# Dual_Driver.net
KiCad netlist of a schematic drawn in EasyEDA Pro
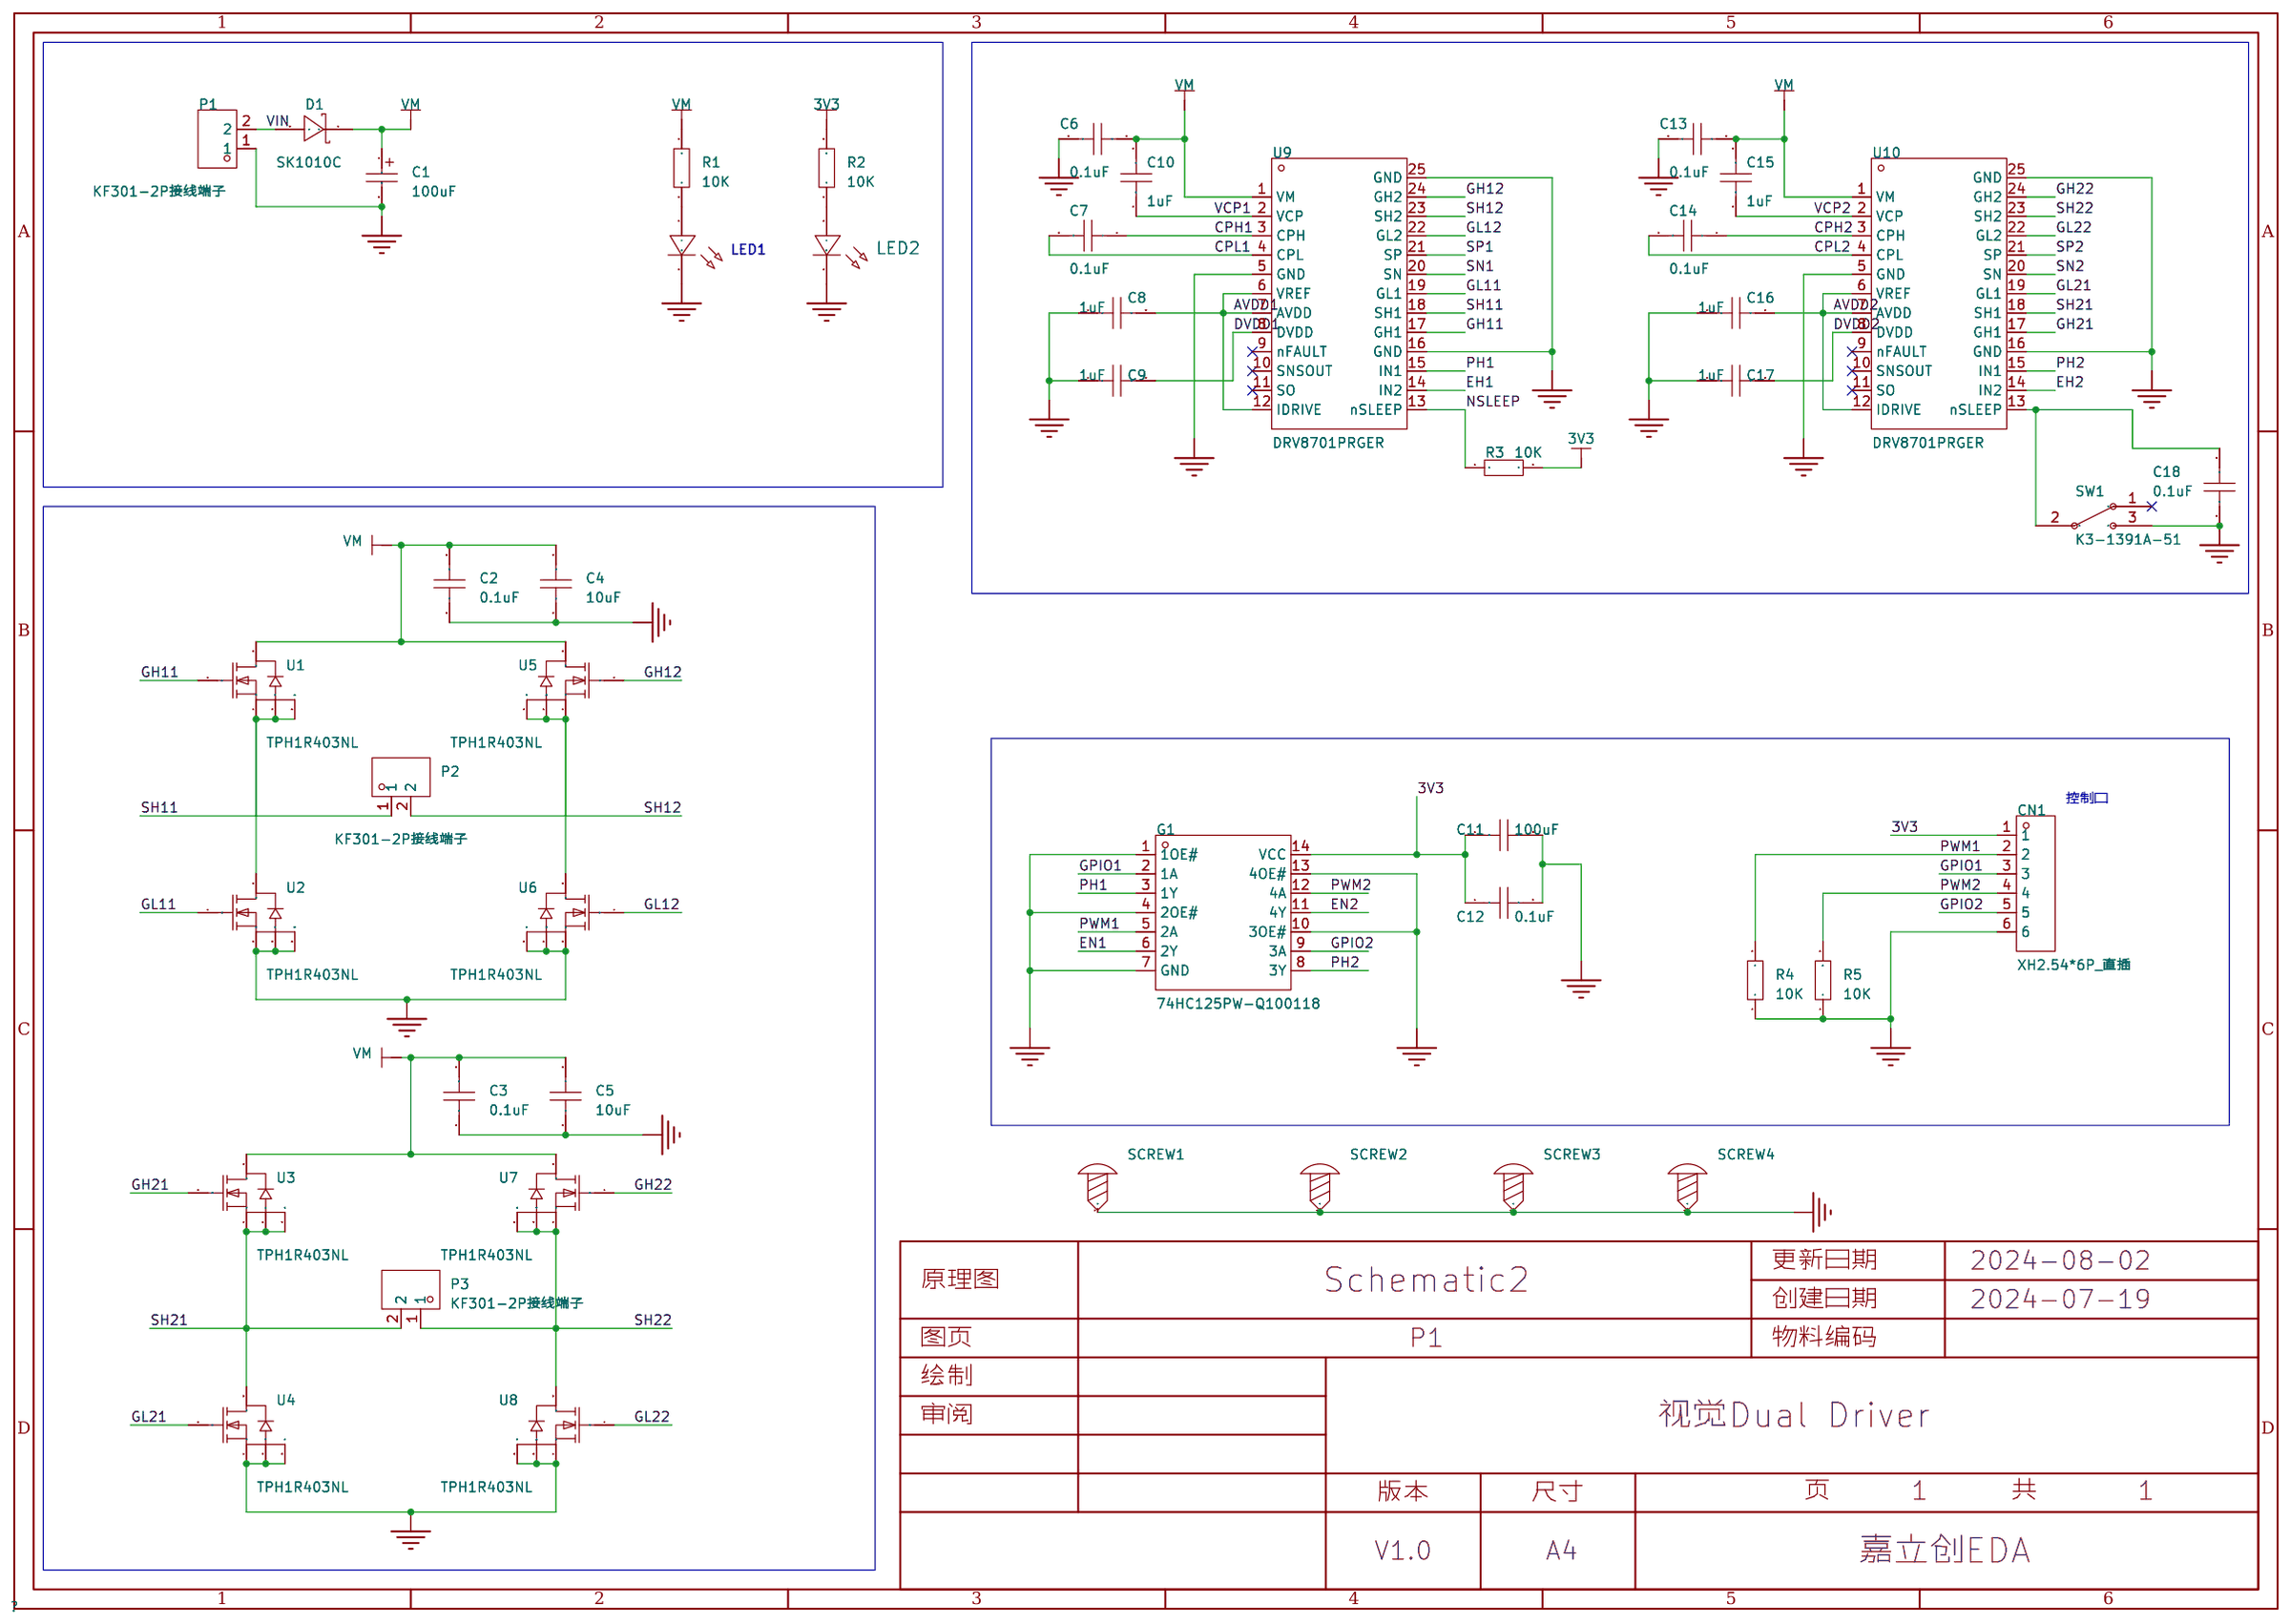
[diagram p0: schematic sheet]

(export (version "E")
  (design (tool "Eeschema 10.0.6"))
  (components
    (comp (ref "C1")
      (value "100uF")
      (footprint "easyedapro:C_Ele_SMD_3x5.4mm")
      (libsource (lib "easyedapro") (part "CAP"))
    )
    (comp (ref "C2")
      (value "0.1uF")
      (footprint "easyedapro:C0603")
      (libsource (lib "easyedapro") (part "CapAcitance"))
    )
    (comp (ref "C3")
      (value "0.1uF")
      (footprint "easyedapro:C0603")
      (libsource (lib "easyedapro") (part "CapAcitance"))
    )
    (comp (ref "C4")
      (value "10uF")
      (footprint "easyedapro:C0603")
      (libsource (lib "easyedapro") (part "CapAcitance"))
    )
    (comp (ref "C5")
      (value "10uF")
      (footprint "easyedapro:C0603")
      (libsource (lib "easyedapro") (part "CapAcitance"))
    )
    (comp (ref "C6")
      (value "0.1uF")
      (footprint "easyedapro:C0603")
      (libsource (lib "easyedapro") (part "CapAcitance"))
    )
    (comp (ref "C7")
      (value "0.1uF")
      (footprint "easyedapro:C0603")
      (libsource (lib "easyedapro") (part "CapAcitance"))
    )
    (comp (ref "C8")
      (value "1uF")
      (footprint "easyedapro:C0603")
      (libsource (lib "easyedapro") (part "CapAcitance"))
    )
    (comp (ref "C9")
      (value "1uF")
      (footprint "easyedapro:C0603")
      (libsource (lib "easyedapro") (part "CapAcitance"))
    )
    (comp (ref "C10")
      (value "1uF")
      (footprint "easyedapro:C0603")
      (libsource (lib "easyedapro") (part "CapAcitance"))
    )
    (comp (ref "C11")
      (value "100uF")
      (footprint "easyedapro:C0603")
      (libsource (lib "easyedapro") (part "CapAcitance"))
    )
    (comp (ref "C12")
      (value "0.1uF")
      (footprint "easyedapro:C0603")
      (libsource (lib "easyedapro") (part "CapAcitance"))
    )
    (comp (ref "C13")
      (value "0.1uF")
      (footprint "easyedapro:C0603")
      (libsource (lib "easyedapro") (part "CapAcitance"))
    )
    (comp (ref "C14")
      (value "0.1uF")
      (footprint "easyedapro:C0603")
      (libsource (lib "easyedapro") (part "CapAcitance"))
    )
    (comp (ref "C15")
      (value "1uF")
      (footprint "easyedapro:C0603")
      (libsource (lib "easyedapro") (part "CapAcitance"))
    )
    (comp (ref "C16")
      (value "1uF")
      (footprint "easyedapro:C0603")
      (libsource (lib "easyedapro") (part "CapAcitance"))
    )
    (comp (ref "C17")
      (value "1uF")
      (footprint "easyedapro:C0603")
      (libsource (lib "easyedapro") (part "CapAcitance"))
    )
    (comp (ref "C18")
      (value "0.1uF")
      (footprint "easyedapro:C0603")
      (libsource (lib "easyedapro") (part "CapAcitance"))
    )
    (comp (ref "CN1")
      (value "XH2.54*6P_直插")
      (footprint "easyedapro:CONN-TH_XH2.54-6P")
      (libsource (lib "easyedapro") (part "XH2.54*6P_直插"))
    )
    (comp (ref "D1")
      (value "SK1010C")
      (footprint "easyedapro:SMC_L7.1-W6.2-LS8.1-RD")
      (description "二极管配置:独立式;正向压降(Vf):850mV@10A;直流反向耐压(Vr):100V;整流电流:10A;")
      (fields (field (name "Manufacturer") "MDD(辰达半导体)"))
      (libsource (lib "easyedapro") (part "SK1010"))
    )
    (comp (ref "G1")
      (value "74HC125PW-Q100118")
      (footprint "easyedapro:TSSOP-14_L5.0-W4.4-P0.65-LS6.4-BL")
      (description "电源电压:2V~6V;每个元件位数:1;灌电流(IOL):7.8mA;拉电流(IOH):7.8mA;")
      (fields (field (name "Manufacturer") "Nexperia(安世)"))
      (libsource (lib "easyedapro") (part "74HC125PW-Q100118"))
    )
    (comp (ref "LED1")
      (value "~")
      (footprint "easyedapro:LED_0603")
      (libsource (lib "easyedapro") (part "LED_G"))
    )
    (comp (ref "LED2")
      (value "~")
      (footprint "easyedapro:LED_0402")
      (libsource (lib "easyedapro") (part "LED_R"))
    )
    (comp (ref "P1")
      (value "KF301-2P接线端子")
      (footprint "easyedapro:CONN-TH_XY301V-A-5.0-2P")
      (libsource (lib "easyedapro") (part "KF301-2P接线端子"))
    )
    (comp (ref "P2")
      (value "KF301-2P接线端子")
      (footprint "easyedapro:CONN-TH_XY301V-A-5.0-2P")
      (libsource (lib "easyedapro") (part "KF301-2P接线端子"))
    )
    (comp (ref "P3")
      (value "KF301-2P接线端子")
      (footprint "easyedapro:CONN-TH_XY301V-A-5.0-2P")
      (libsource (lib "easyedapro") (part "KF301-2P接线端子"))
    )
    (comp (ref "R1") (value "10K") (footprint "easyedapro:R0603") (libsource (lib "easyedapro") (part "电阻")))
    (comp (ref "R2") (value "10K") (footprint "easyedapro:R0603") (libsource (lib "easyedapro") (part "电阻")))
    (comp (ref "R3") (value "10K") (footprint "easyedapro:R0603") (libsource (lib "easyedapro") (part "电阻")))
    (comp (ref "R4") (value "10K") (footprint "easyedapro:R0603") (libsource (lib "easyedapro") (part "电阻")))
    (comp (ref "R5") (value "10K") (footprint "easyedapro:R0603") (libsource (lib "easyedapro") (part "电阻")))
    (comp (ref "SCREW1")
      (value "~")
      (footprint "easyedapro:M2螺丝")
      (libsource (lib "easyedapro") (part "螺丝孔"))
    )
    (comp (ref "SCREW2")
      (value "~")
      (footprint "easyedapro:M2螺丝")
      (libsource (lib "easyedapro") (part "螺丝孔"))
    )
    (comp (ref "SCREW3")
      (value "~")
      (footprint "easyedapro:M2螺丝")
      (libsource (lib "easyedapro") (part "螺丝孔"))
    )
    (comp (ref "SCREW4")
      (value "~")
      (footprint "easyedapro:M2螺丝")
      (libsource (lib "easyedapro") (part "螺丝孔"))
    )
    (comp (ref "SW1")
      (value "K3-1391A-51")
      (footprint "easyedapro:SW-TH_K3-1391A")
      (description "电路结构:单刀双掷;安装方式:直插;开关颜色:黑色;额定电压(DC):-;额定电流(AC):5A;额定电压(AC):120V;机械寿命:3万次;")
      (fields (field (name "Manufacturer") "韩国韩荣"))
      (libsource (lib "easyedapro") (part "K3-1391A"))
    )
    (comp (ref "U1")
      (value "TPH1R403NL")
      (footprint "easyedapro:TDSON-8_L5.9-W5.2-P1.27-BL")
      (fields (field (name "Manufacturer") "TECH PUBLIC(台舟)"))
      (libsource (lib "easyedapro") (part "TPH1R403NL_C19268167"))
    )
    (comp (ref "U2")
      (value "TPH1R403NL")
      (footprint "easyedapro:TDSON-8_L5.9-W5.2-P1.27-BL")
      (fields (field (name "Manufacturer") "TECH PUBLIC(台舟)"))
      (libsource (lib "easyedapro") (part "TPH1R403NL_C19268167"))
    )
    (comp (ref "U3")
      (value "TPH1R403NL")
      (footprint "easyedapro:TDSON-8_L5.9-W5.2-P1.27-BL")
      (fields (field (name "Manufacturer") "TECH PUBLIC(台舟)"))
      (libsource (lib "easyedapro") (part "TPH1R403NL_C19268167"))
    )
    (comp (ref "U4")
      (value "TPH1R403NL")
      (footprint "easyedapro:TDSON-8_L5.9-W5.2-P1.27-BL")
      (fields (field (name "Manufacturer") "TECH PUBLIC(台舟)"))
      (libsource (lib "easyedapro") (part "TPH1R403NL_C19268167"))
    )
    (comp (ref "U5")
      (value "TPH1R403NL")
      (footprint "easyedapro:TDSON-8_L5.9-W5.2-P1.27-BL")
      (fields (field (name "Manufacturer") "TECH PUBLIC(台舟)"))
      (libsource (lib "easyedapro") (part "TPH1R403NL_C19268167"))
    )
    (comp (ref "U6")
      (value "TPH1R403NL")
      (footprint "easyedapro:TDSON-8_L5.9-W5.2-P1.27-BL")
      (fields (field (name "Manufacturer") "TECH PUBLIC(台舟)"))
      (libsource (lib "easyedapro") (part "TPH1R403NL_C19268167"))
    )
    (comp (ref "U7")
      (value "TPH1R403NL")
      (footprint "easyedapro:TDSON-8_L5.9-W5.2-P1.27-BL")
      (fields (field (name "Manufacturer") "TECH PUBLIC(台舟)"))
      (libsource (lib "easyedapro") (part "TPH1R403NL_C19268167"))
    )
    (comp (ref "U8")
      (value "TPH1R403NL")
      (footprint "easyedapro:TDSON-8_L5.9-W5.2-P1.27-BL")
      (fields (field (name "Manufacturer") "TECH PUBLIC(台舟)"))
      (libsource (lib "easyedapro") (part "TPH1R403NL_C19268167"))
    )
    (comp (ref "U9")
      (value "DRV8701PRGER")
      (footprint "easyedapro:VQFN-24_L4.0-W4.0-P0.50-BL-EP2.8")
      (description "DRV8701 47V H 桥智能栅极驱动器")
      (fields (field (name "Manufacturer") "TI(德州仪器)"))
      (libsource (lib "easyedapro") (part "DRV8701PRGER"))
    )
    (comp (ref "U10")
      (value "DRV8701PRGER")
      (footprint "easyedapro:VQFN-24_L4.0-W4.0-P0.50-BL-EP2.8")
      (description "DRV8701 47V H 桥智能栅极驱动器")
      (fields (field (name "Manufacturer") "TI(德州仪器)"))
      (libsource (lib "easyedapro") (part "DRV8701PRGER"))
    )
  )
  (nets
    (net (code "1") (name "/AVDD1") (class "Default")
      (node (ref "C8") (pin "2") (pinfunction "2_2") (pintype "input"))
      (node (ref "U9") (pin "12") (pinfunction "IDRIVE_12") (pintype "unspecified"))
      (node (ref "U9") (pin "6") (pinfunction "VREF_6") (pintype "unspecified"))
      (node (ref "U9") (pin "7") (pinfunction "AVDD_7") (pintype "unspecified"))
    )
    (net (code "2") (name "/AVDD2") (class "Default")
      (node (ref "C16") (pin "2") (pinfunction "2_2") (pintype "input"))
      (node (ref "U10") (pin "12") (pinfunction "IDRIVE_12") (pintype "unspecified"))
      (node (ref "U10") (pin "6") (pinfunction "VREF_6") (pintype "unspecified"))
      (node (ref "U10") (pin "7") (pinfunction "AVDD_7") (pintype "unspecified"))
    )
    (net (code "3") (name "/CPH1") (class "Default")
      (node (ref "C7") (pin "1") (pinfunction "1_1") (pintype "input"))
      (node (ref "U9") (pin "3") (pinfunction "CPH_3") (pintype "unspecified"))
    )
    (net (code "4") (name "/CPH2") (class "Default")
      (node (ref "C14") (pin "1") (pinfunction "1_1") (pintype "input"))
      (node (ref "U10") (pin "3") (pinfunction "CPH_3") (pintype "unspecified"))
    )
    (net (code "5") (name "/CPL1") (class "Default")
      (node (ref "C7") (pin "2") (pinfunction "2_2") (pintype "input"))
      (node (ref "U9") (pin "4") (pinfunction "CPL_4") (pintype "unspecified"))
    )
    (net (code "6") (name "/CPL2") (class "Default")
      (node (ref "C14") (pin "2") (pinfunction "2_2") (pintype "input"))
      (node (ref "U10") (pin "4") (pinfunction "CPL_4") (pintype "unspecified"))
    )
    (net (code "7") (name "/DVDD1") (class "Default")
      (node (ref "C9") (pin "2") (pinfunction "2_2") (pintype "input"))
      (node (ref "U9") (pin "8") (pinfunction "DVDD_8") (pintype "unspecified"))
    )
    (net (code "8") (name "/DVDD2") (class "Default")
      (node (ref "C17") (pin "2") (pinfunction "2_2") (pintype "input"))
      (node (ref "U10") (pin "8") (pinfunction "DVDD_8") (pintype "unspecified"))
    )
    (net (code "9") (name "/EH1") (class "Default")
      (node (ref "U9") (pin "14") (pinfunction "IN2_14") (pintype "unspecified"))
    )
    (net (code "10") (name "/EH2") (class "Default")
      (node (ref "U10") (pin "14") (pinfunction "IN2_14") (pintype "unspecified"))
    )
    (net (code "11") (name "/EN1") (class "Default")
      (node (ref "G1") (pin "6") (pinfunction "2Y_6") (pintype "unspecified"))
    )
    (net (code "12") (name "/EN2") (class "Default")
      (node (ref "G1") (pin "11") (pinfunction "4Y_11") (pintype "unspecified"))
    )
    (net (code "13") (name "/GH11") (class "Default")
      (node (ref "U1") (pin "4") (pinfunction "G_4") (pintype "unspecified"))
      (node (ref "U9") (pin "17") (pinfunction "GH1_17") (pintype "unspecified"))
    )
    (net (code "14") (name "/GH12") (class "Default")
      (node (ref "U5") (pin "4") (pinfunction "G_4") (pintype "unspecified"))
      (node (ref "U9") (pin "24") (pinfunction "GH2_24") (pintype "unspecified"))
    )
    (net (code "15") (name "/GH21") (class "Default")
      (node (ref "U10") (pin "17") (pinfunction "GH1_17") (pintype "unspecified"))
      (node (ref "U3") (pin "4") (pinfunction "G_4") (pintype "unspecified"))
    )
    (net (code "16") (name "/GH22") (class "Default")
      (node (ref "U10") (pin "24") (pinfunction "GH2_24") (pintype "unspecified"))
      (node (ref "U7") (pin "4") (pinfunction "G_4") (pintype "unspecified"))
    )
    (net (code "17") (name "/GL11") (class "Default")
      (node (ref "U2") (pin "4") (pinfunction "G_4") (pintype "unspecified"))
      (node (ref "U9") (pin "19") (pinfunction "GL1_19") (pintype "unspecified"))
    )
    (net (code "18") (name "/GL12") (class "Default")
      (node (ref "U6") (pin "4") (pinfunction "G_4") (pintype "unspecified"))
      (node (ref "U9") (pin "22") (pinfunction "GL2_22") (pintype "unspecified"))
    )
    (net (code "19") (name "/GL21") (class "Default")
      (node (ref "U10") (pin "19") (pinfunction "GL1_19") (pintype "unspecified"))
      (node (ref "U4") (pin "4") (pinfunction "G_4") (pintype "unspecified"))
    )
    (net (code "20") (name "/GL22") (class "Default")
      (node (ref "U10") (pin "22") (pinfunction "GL2_22") (pintype "unspecified"))
      (node (ref "U8") (pin "4") (pinfunction "G_4") (pintype "unspecified"))
    )
    (net (code "21") (name "/GPIO1") (class "Default")
      (node (ref "CN1") (pin "3") (pinfunction "3_3") (pintype "unspecified"))
      (node (ref "G1") (pin "2") (pinfunction "1A_2") (pintype "unspecified"))
    )
    (net (code "22") (name "/GPIO2") (class "Default")
      (node (ref "CN1") (pin "5") (pinfunction "5_5") (pintype "unspecified"))
      (node (ref "G1") (pin "9") (pinfunction "3A_9") (pintype "unspecified"))
    )
    (net (code "23") (name "/NSLEEP") (class "Default")
      (node (ref "R3") (pin "1") (pinfunction "1_1") (pintype "input"))
      (node (ref "U9") (pin "13") (pinfunction "nSLEEP_13") (pintype "unspecified"))
    )
    (net (code "24") (name "/PH1") (class "Default")
      (node (ref "G1") (pin "3") (pinfunction "1Y_3") (pintype "unspecified"))
      (node (ref "U9") (pin "15") (pinfunction "IN1_15") (pintype "unspecified"))
    )
    (net (code "25") (name "/PH2") (class "Default")
      (node (ref "G1") (pin "8") (pinfunction "3Y_8") (pintype "unspecified"))
      (node (ref "U10") (pin "15") (pinfunction "IN1_15") (pintype "unspecified"))
    )
    (net (code "26") (name "/PWM1") (class "Default")
      (node (ref "CN1") (pin "2") (pinfunction "2_2") (pintype "unspecified"))
      (node (ref "G1") (pin "5") (pinfunction "2A_5") (pintype "unspecified"))
      (node (ref "R4") (pin "2") (pinfunction "2_2") (pintype "input"))
    )
    (net (code "27") (name "/PWM2") (class "Default")
      (node (ref "CN1") (pin "4") (pinfunction "4_4") (pintype "unspecified"))
      (node (ref "G1") (pin "12") (pinfunction "4A_12") (pintype "unspecified"))
      (node (ref "R5") (pin "2") (pinfunction "2_2") (pintype "input"))
    )
    (net (code "28") (name "/SH11") (class "Default")
      (node (ref "P2") (pin "1") (pinfunction "1_1") (pintype "unspecified"))
      (node (ref "U1") (pin "1") (pinfunction "S_1") (pintype "unspecified"))
      (node (ref "U1") (pin "2") (pinfunction "S_2") (pintype "unspecified"))
      (node (ref "U1") (pin "3") (pinfunction "S_3") (pintype "unspecified"))
      (node (ref "U2") (pin "5") (pinfunction "D_5") (pintype "unspecified"))
      (node (ref "U9") (pin "18") (pinfunction "SH1_18") (pintype "unspecified"))
    )
    (net (code "29") (name "/SH12") (class "Default")
      (node (ref "P2") (pin "2") (pinfunction "2_2") (pintype "unspecified"))
      (node (ref "U5") (pin "1") (pinfunction "S_1") (pintype "unspecified"))
      (node (ref "U5") (pin "2") (pinfunction "S_2") (pintype "unspecified"))
      (node (ref "U5") (pin "3") (pinfunction "S_3") (pintype "unspecified"))
      (node (ref "U6") (pin "5") (pinfunction "D_5") (pintype "unspecified"))
      (node (ref "U9") (pin "23") (pinfunction "SH2_23") (pintype "unspecified"))
    )
    (net (code "30") (name "/SH21") (class "Default")
      (node (ref "P3") (pin "2") (pinfunction "2_2") (pintype "unspecified"))
      (node (ref "U10") (pin "18") (pinfunction "SH1_18") (pintype "unspecified"))
      (node (ref "U3") (pin "1") (pinfunction "S_1") (pintype "unspecified"))
      (node (ref "U3") (pin "2") (pinfunction "S_2") (pintype "unspecified"))
      (node (ref "U3") (pin "3") (pinfunction "S_3") (pintype "unspecified"))
      (node (ref "U4") (pin "5") (pinfunction "D_5") (pintype "unspecified"))
    )
    (net (code "31") (name "/SH22") (class "Default")
      (node (ref "P3") (pin "1") (pinfunction "1_1") (pintype "unspecified"))
      (node (ref "U10") (pin "23") (pinfunction "SH2_23") (pintype "unspecified"))
      (node (ref "U7") (pin "1") (pinfunction "S_1") (pintype "unspecified"))
      (node (ref "U7") (pin "2") (pinfunction "S_2") (pintype "unspecified"))
      (node (ref "U7") (pin "3") (pinfunction "S_3") (pintype "unspecified"))
      (node (ref "U8") (pin "5") (pinfunction "D_5") (pintype "unspecified"))
    )
    (net (code "32") (name "/SN1") (class "Default")
      (node (ref "U9") (pin "20") (pinfunction "SN_20") (pintype "unspecified"))
    )
    (net (code "33") (name "/SN2") (class "Default")
      (node (ref "U10") (pin "20") (pinfunction "SN_20") (pintype "unspecified"))
    )
    (net (code "34") (name "/SP1") (class "Default")
      (node (ref "U9") (pin "21") (pinfunction "SP_21") (pintype "unspecified"))
    )
    (net (code "35") (name "/SP2") (class "Default")
      (node (ref "U10") (pin "21") (pinfunction "SP_21") (pintype "unspecified"))
    )
    (net (code "36") (name "/VCP1") (class "Default")
      (node (ref "C10") (pin "1") (pinfunction "1_1") (pintype "input"))
      (node (ref "U9") (pin "2") (pinfunction "VCP_2") (pintype "unspecified"))
    )
    (net (code "37") (name "/VCP2") (class "Default")
      (node (ref "C15") (pin "1") (pinfunction "1_1") (pintype "input"))
      (node (ref "U10") (pin "2") (pinfunction "VCP_2") (pintype "unspecified"))
    )
    (net (code "38") (name "/VIN") (class "Default")
      (node (ref "D1") (pin "2") (pinfunction "A_2") (pintype "unspecified"))
      (node (ref "P1") (pin "2") (pinfunction "2_2") (pintype "unspecified"))
    )
    (net (code "39") (name "3V3") (class "Default")
      (node (ref "C11") (pin "1") (pinfunction "1_1") (pintype "input"))
      (node (ref "C12") (pin "1") (pinfunction "1_1") (pintype "input"))
      (node (ref "CN1") (pin "1") (pinfunction "1_1") (pintype "unspecified"))
      (node (ref "G1") (pin "14") (pinfunction "VCC_14") (pintype "unspecified"))
      (node (ref "R2") (pin "2") (pinfunction "2_2") (pintype "input"))
      (node (ref "R3") (pin "2") (pinfunction "2_2") (pintype "input"))
    )
    (net (code "40") (name "GND") (class "Default")
      (node (ref "C1") (pin "2") (pinfunction "2_2") (pintype "input"))
      (node (ref "C11") (pin "2") (pinfunction "2_2") (pintype "input"))
      (node (ref "C12") (pin "2") (pinfunction "2_2") (pintype "input"))
      (node (ref "C13") (pin "2") (pinfunction "2_2") (pintype "input"))
      (node (ref "C16") (pin "1") (pinfunction "1_1") (pintype "input"))
      (node (ref "C17") (pin "1") (pinfunction "1_1") (pintype "input"))
      (node (ref "C18") (pin "1") (pinfunction "1_1") (pintype "input"))
      (node (ref "C2") (pin "1") (pinfunction "1_1") (pintype "input"))
      (node (ref "C3") (pin "1") (pinfunction "1_1") (pintype "input"))
      (node (ref "C4") (pin "1") (pinfunction "1_1") (pintype "input"))
      (node (ref "C5") (pin "1") (pinfunction "1_1") (pintype "input"))
      (node (ref "C6") (pin "2") (pinfunction "2_2") (pintype "input"))
      (node (ref "C8") (pin "1") (pinfunction "1_1") (pintype "input"))
      (node (ref "C9") (pin "1") (pinfunction "1_1") (pintype "input"))
      (node (ref "CN1") (pin "6") (pinfunction "6_6") (pintype "unspecified"))
      (node (ref "G1") (pin "1") (pinfunction "1OE#_1") (pintype "unspecified"))
      (node (ref "G1") (pin "10") (pinfunction "3OE#_10") (pintype "unspecified"))
      (node (ref "G1") (pin "13") (pinfunction "4OE#_13") (pintype "unspecified"))
      (node (ref "G1") (pin "4") (pinfunction "2OE#_4") (pintype "unspecified"))
      (node (ref "G1") (pin "7") (pinfunction "GND_7") (pintype "unspecified"))
      (node (ref "LED1") (pin "1") (pinfunction "C_1") (pintype "input"))
      (node (ref "LED2") (pin "1") (pinfunction "C_1") (pintype "input"))
      (node (ref "P1") (pin "1") (pinfunction "1_1") (pintype "unspecified"))
      (node (ref "R4") (pin "1") (pinfunction "1_1") (pintype "input"))
      (node (ref "R5") (pin "1") (pinfunction "1_1") (pintype "input"))
      (node (ref "SCREW1") (pin "1") (pinfunction "1_1") (pintype "input"))
      (node (ref "SCREW2") (pin "1") (pinfunction "1_1") (pintype "input"))
      (node (ref "SCREW3") (pin "1") (pinfunction "1_1") (pintype "input"))
      (node (ref "SCREW4") (pin "1") (pinfunction "1_1") (pintype "input"))
      (node (ref "SW1") (pin "3") (pinfunction "3_3") (pintype "input"))
      (node (ref "U10") (pin "16") (pinfunction "GND_16") (pintype "unspecified"))
      (node (ref "U10") (pin "25") (pinfunction "GND_25") (pintype "unspecified"))
      (node (ref "U10") (pin "5") (pinfunction "GND_5") (pintype "unspecified"))
      (node (ref "U2") (pin "1") (pinfunction "S_1") (pintype "unspecified"))
      (node (ref "U2") (pin "2") (pinfunction "S_2") (pintype "unspecified"))
      (node (ref "U2") (pin "3") (pinfunction "S_3") (pintype "unspecified"))
      (node (ref "U4") (pin "1") (pinfunction "S_1") (pintype "unspecified"))
      (node (ref "U4") (pin "2") (pinfunction "S_2") (pintype "unspecified"))
      (node (ref "U4") (pin "3") (pinfunction "S_3") (pintype "unspecified"))
      (node (ref "U6") (pin "1") (pinfunction "S_1") (pintype "unspecified"))
      (node (ref "U6") (pin "2") (pinfunction "S_2") (pintype "unspecified"))
      (node (ref "U6") (pin "3") (pinfunction "S_3") (pintype "unspecified"))
      (node (ref "U8") (pin "1") (pinfunction "S_1") (pintype "unspecified"))
      (node (ref "U8") (pin "2") (pinfunction "S_2") (pintype "unspecified"))
      (node (ref "U8") (pin "3") (pinfunction "S_3") (pintype "unspecified"))
      (node (ref "U9") (pin "16") (pinfunction "GND_16") (pintype "unspecified"))
      (node (ref "U9") (pin "25") (pinfunction "GND_25") (pintype "unspecified"))
      (node (ref "U9") (pin "5") (pinfunction "GND_5") (pintype "unspecified"))
    )
    (net (code "41") (name "Net-(LED1-A)") (class "Default")
      (node (ref "LED1") (pin "2") (pinfunction "A_2") (pintype "input"))
      (node (ref "R1") (pin "1") (pinfunction "1_1") (pintype "input"))
    )
    (net (code "42") (name "Net-(LED2-A)") (class "Default")
      (node (ref "LED2") (pin "2") (pinfunction "A_2") (pintype "input"))
      (node (ref "R2") (pin "1") (pinfunction "1_1") (pintype "input"))
    )
    (net (code "43") (name "Net-(U10-nSLEEP)") (class "Default")
      (node (ref "C18") (pin "2") (pinfunction "2_2") (pintype "input"))
      (node (ref "SW1") (pin "2") (pinfunction "2_2") (pintype "input"))
      (node (ref "U10") (pin "13") (pinfunction "nSLEEP_13") (pintype "unspecified"))
    )
    (net (code "44") (name "VM") (class "Default")
      (node (ref "C1") (pin "1") (pinfunction "1_1") (pintype "input"))
      (node (ref "C10") (pin "2") (pinfunction "2_2") (pintype "input"))
      (node (ref "C13") (pin "1") (pinfunction "1_1") (pintype "input"))
      (node (ref "C15") (pin "2") (pinfunction "2_2") (pintype "input"))
      (node (ref "C2") (pin "2") (pinfunction "2_2") (pintype "input"))
      (node (ref "C3") (pin "2") (pinfunction "2_2") (pintype "input"))
      (node (ref "C4") (pin "2") (pinfunction "2_2") (pintype "input"))
      (node (ref "C5") (pin "2") (pinfunction "2_2") (pintype "input"))
      (node (ref "C6") (pin "1") (pinfunction "1_1") (pintype "input"))
      (node (ref "D1") (pin "1") (pinfunction "K_1") (pintype "unspecified"))
      (node (ref "R1") (pin "2") (pinfunction "2_2") (pintype "input"))
      (node (ref "U1") (pin "5") (pinfunction "D_5") (pintype "unspecified"))
      (node (ref "U10") (pin "1") (pinfunction "VM_1") (pintype "unspecified"))
      (node (ref "U3") (pin "5") (pinfunction "D_5") (pintype "unspecified"))
      (node (ref "U5") (pin "5") (pinfunction "D_5") (pintype "unspecified"))
      (node (ref "U7") (pin "5") (pinfunction "D_5") (pintype "unspecified"))
      (node (ref "U9") (pin "1") (pinfunction "VM_1") (pintype "unspecified"))
    )
    (net (code "45") (name "unconnected-(SW1-Pad1)") (class "Default")
      (node (ref "SW1") (pin "1") (pinfunction "1_1") (pintype "input+no_connect"))
    )
    (net (code "46") (name "unconnected-(U9-SNSOUT-Pad10)") (class "Default")
      (node (ref "U9") (pin "10") (pinfunction "SNSOUT_10") (pintype "unspecified+no_connect"))
    )
    (net (code "47") (name "unconnected-(U9-SO-Pad11)") (class "Default")
      (node (ref "U9") (pin "11") (pinfunction "SO_11") (pintype "unspecified+no_connect"))
    )
    (net (code "48") (name "unconnected-(U9-nFAULT-Pad9)") (class "Default")
      (node (ref "U9") (pin "9") (pinfunction "nFAULT_9") (pintype "unspecified+no_connect"))
    )
    (net (code "49") (name "unconnected-(U10-SNSOUT-Pad10)") (class "Default")
      (node (ref "U10") (pin "10") (pinfunction "SNSOUT_10") (pintype "unspecified+no_connect"))
    )
    (net (code "50") (name "unconnected-(U10-SO-Pad11)") (class "Default")
      (node (ref "U10") (pin "11") (pinfunction "SO_11") (pintype "unspecified+no_connect"))
    )
    (net (code "51") (name "unconnected-(U10-nFAULT-Pad9)") (class "Default")
      (node (ref "U10") (pin "9") (pinfunction "nFAULT_9") (pintype "unspecified+no_connect"))
    )
  )
)
